# Startgate_Controller_Motherboard.net
KiCad netlist of a schematic drawn in EAGLE
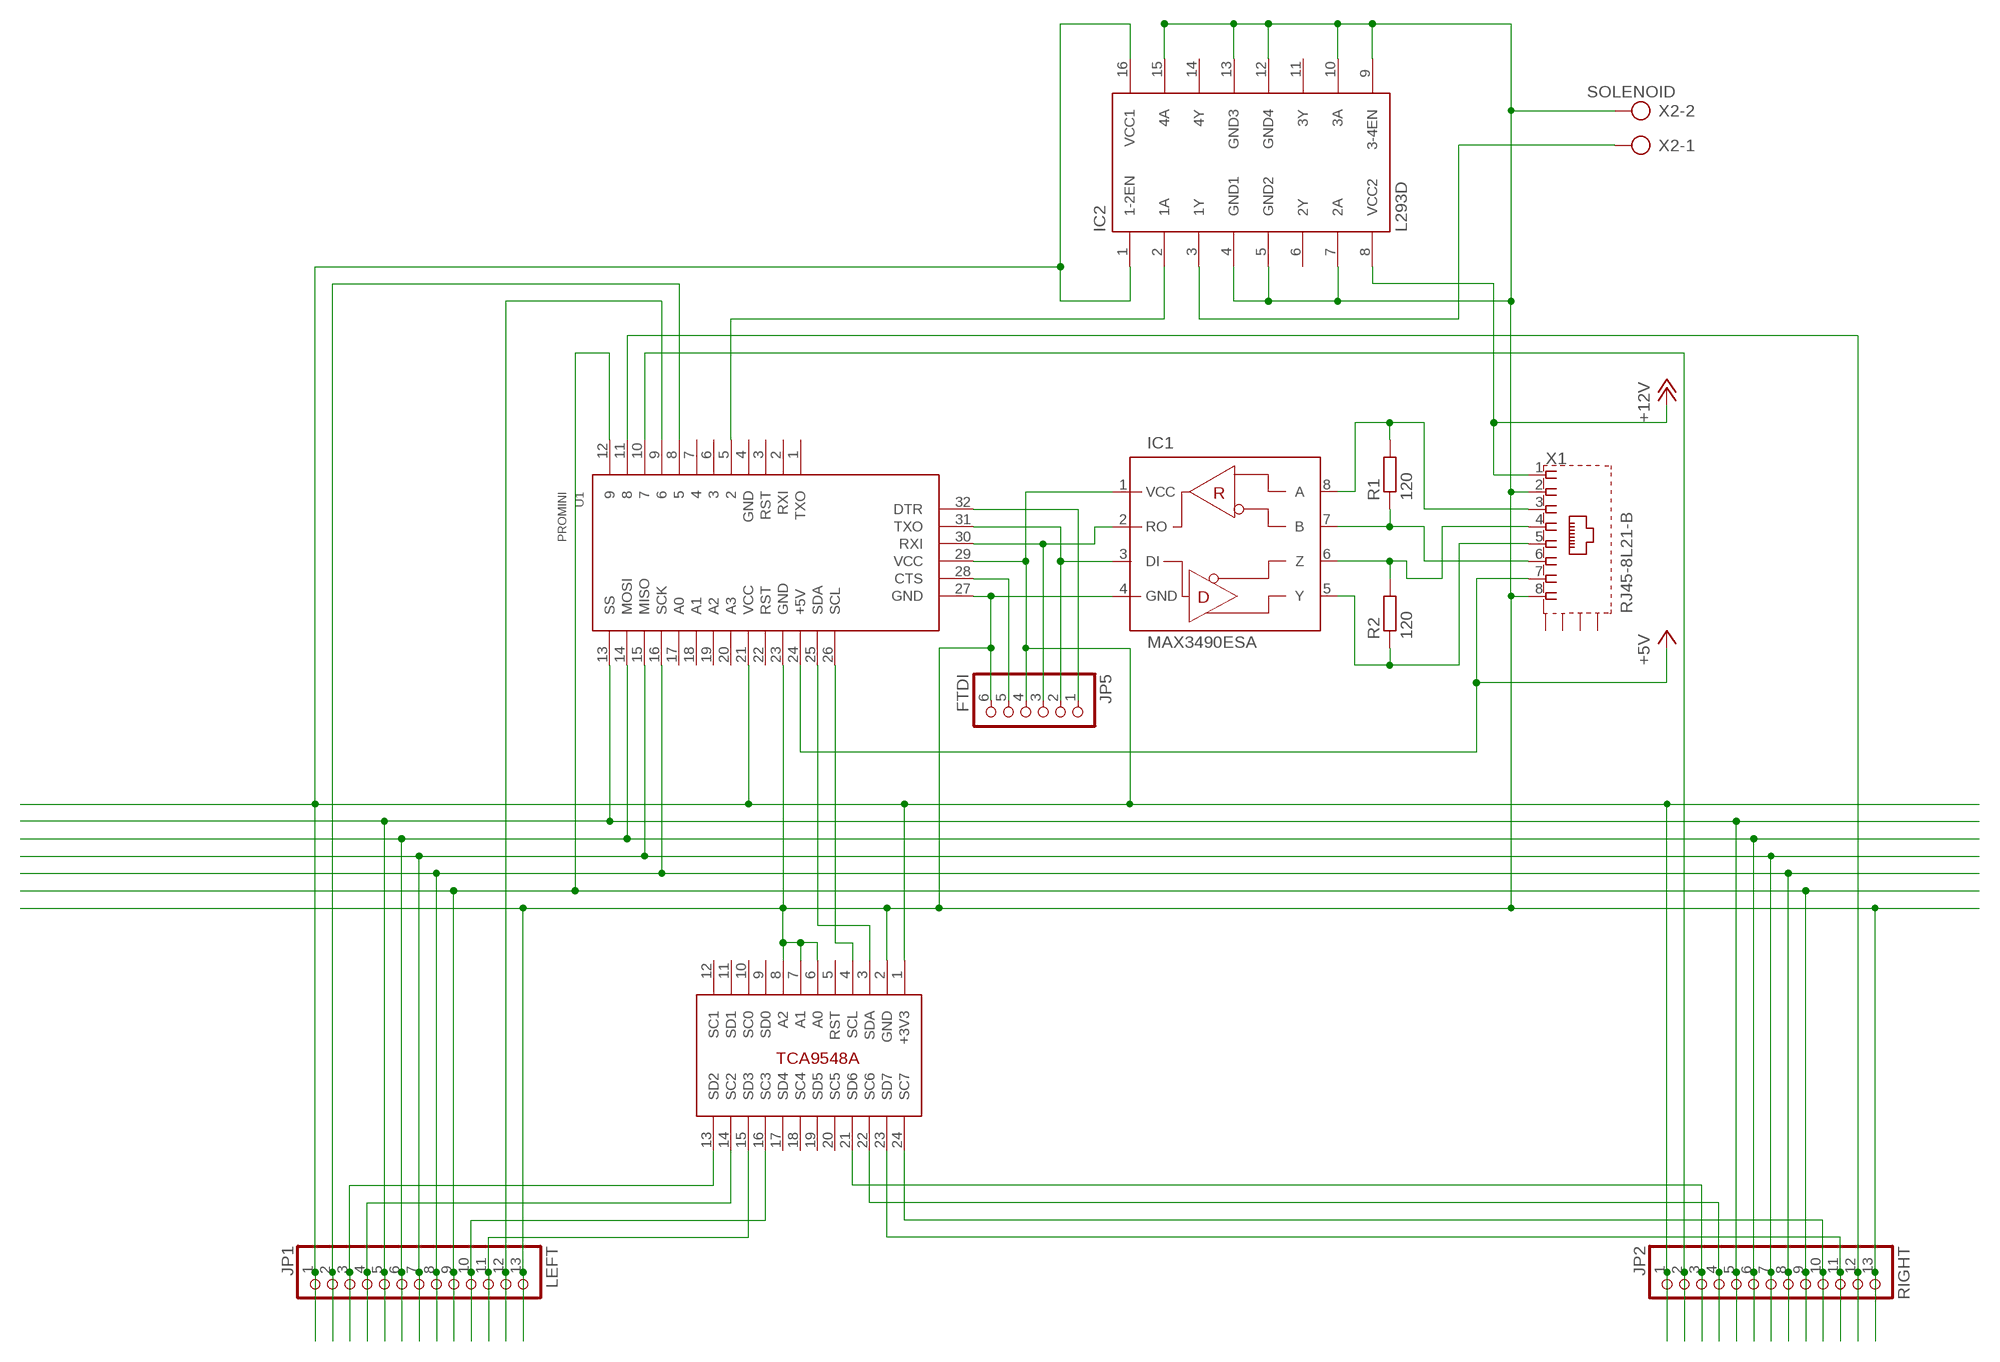
[diagram p0: schematic, sheet 1]

(export (version "E")
  (design (tool "Eeschema 10.0.6"))
  (components
    (comp (ref "IC1")
      (value "MAX3490ESA")
      (footprint "eagle-import:SO08")
      (libsource (lib "eagle-import") (part "MAX3490ESA"))
    )
    (comp (ref "IC2")
      (value "L293D")
      (footprint "eagle-import:DIL16")
      (libsource (lib "eagle-import") (part "L293D"))
    )
    (comp (ref "JP1")
      (value "LEFT")
      (footprint "eagle-import:1X13")
      (libsource (lib "eagle-import") (part "PINHD-1X13"))
    )
    (comp (ref "JP2")
      (value "RIGHT")
      (footprint "eagle-import:1X13")
      (libsource (lib "eagle-import") (part "PINHD-1X13"))
    )
    (comp (ref "JP5")
      (value "FTDI")
      (footprint "eagle-import:1X06")
      (libsource (lib "eagle-import") (part "PINHD-1X6"))
    )
    (comp (ref "R1")
      (value "120")
      (footprint "eagle-import:R0805")
      (libsource (lib "eagle-import") (part "R-EU_R0805"))
    )
    (comp (ref "R2")
      (value "120")
      (footprint "eagle-import:R0805")
      (libsource (lib "eagle-import") (part "R-EU_R0805"))
    )
    (comp (ref "U1")
      (value "PROMINI")
      (footprint "eagle-import:ARDUINOPROMINI")
      (libsource (lib "eagle-import") (part "ARDUINOPROMINI"))
    )
    (comp (ref "U2")
      (value "TCA9548A")
      (footprint "eagle-import:DIL24")
      (libsource (lib "eagle-import") (part "TCA9548A"))
    )
    (comp (ref "X1")
      (value "RJ45-8L21-B")
      (footprint "eagle-import:RJ45-SHIELD1")
      (libsource (lib "eagle-import") (part "RJ4521-B-8L"))
    )
    (comp (ref "X2")
      (value "SOLENOID")
      (footprint "eagle-import:AK300_2")
      (libsource (lib "eagle-import") (part "AK300/2"))
    )
  )
  (nets
    (net (code "1") (name "+5V") (class "Default")
      (node (ref "U1") (pin "24") (pinfunction "+5V_24") (pintype "power_in"))
      (node (ref "X1") (pin "7") (pinfunction "7_7") (pintype "passive"))
    )
    (net (code "2") (name "+12V") (class "Default")
      (node (ref "IC2") (pin "8") (pinfunction "VCC2_8") (pintype "power_in"))
      (node (ref "X1") (pin "1") (pinfunction "1_1") (pintype "passive"))
    )
    (net (code "3") (name "Net-(IC1-A)") (class "Default")
      (node (ref "IC1") (pin "8") (pinfunction "A_8") (pintype "input"))
      (node (ref "R1") (pin "2") (pinfunction "2_2") (pintype "passive"))
      (node (ref "X1") (pin "3") (pinfunction "3_3") (pintype "passive"))
    )
    (net (code "4") (name "Net-(IC1-B)") (class "Default")
      (node (ref "IC1") (pin "7") (pinfunction "B_7") (pintype "input"))
      (node (ref "R1") (pin "1") (pinfunction "1_1") (pintype "passive"))
      (node (ref "X1") (pin "6") (pinfunction "6_6") (pintype "passive"))
    )
    (net (code "5") (name "Net-(IC1-DI)") (class "Default")
      (node (ref "IC1") (pin "3") (pinfunction "DI_3") (pintype "input"))
      (node (ref "JP5") (pin "2") (pinfunction "2_2") (pintype "passive"))
      (node (ref "U1") (pin "31") (pinfunction "TXO_31") (pintype "bidirectional"))
    )
    (net (code "6") (name "Net-(IC1-GND)") (class "Default")
      (node (ref "IC1") (pin "4") (pinfunction "GND_4") (pintype "power_in"))
      (node (ref "IC2") (pin "10") (pinfunction "3A_10") (pintype "input"))
      (node (ref "IC2") (pin "12") (pinfunction "GND4_12") (pintype "power_in"))
      (node (ref "IC2") (pin "13") (pinfunction "GND3_13") (pintype "power_in"))
      (node (ref "IC2") (pin "15") (pinfunction "4A_15") (pintype "input"))
      (node (ref "IC2") (pin "4") (pinfunction "GND1_4") (pintype "power_in"))
      (node (ref "IC2") (pin "5") (pinfunction "GND2_5") (pintype "power_in"))
      (node (ref "IC2") (pin "7") (pinfunction "2A_7") (pintype "input"))
      (node (ref "IC2") (pin "9") (pinfunction "3-4EN_9") (pintype "input"))
      (node (ref "JP1") (pin "13") (pinfunction "13_13") (pintype "passive"))
      (node (ref "JP2") (pin "13") (pinfunction "13_13") (pintype "passive"))
      (node (ref "JP5") (pin "6") (pinfunction "6_6") (pintype "passive"))
      (node (ref "U1") (pin "23") (pinfunction "GND_23") (pintype "bidirectional"))
      (node (ref "U1") (pin "27") (pinfunction "GND_27") (pintype "bidirectional"))
      (node (ref "U2") (pin "2") (pinfunction "GND_2") (pintype "power_in"))
      (node (ref "U2") (pin "6") (pinfunction "A0_6") (pintype "bidirectional"))
      (node (ref "U2") (pin "7") (pinfunction "A1_7") (pintype "bidirectional"))
      (node (ref "U2") (pin "8") (pinfunction "A2_8") (pintype "bidirectional"))
      (node (ref "X1") (pin "2") (pinfunction "2_2") (pintype "passive"))
      (node (ref "X1") (pin "8") (pinfunction "8_8") (pintype "passive"))
      (node (ref "X2") (pin "2") (pinfunction "KL_2") (pintype "passive"))
    )
    (net (code "7") (name "Net-(IC1-RO)") (class "Default")
      (node (ref "IC1") (pin "2") (pinfunction "RO_2") (pintype "output"))
      (node (ref "JP5") (pin "3") (pinfunction "3_3") (pintype "passive"))
      (node (ref "U1") (pin "30") (pinfunction "RXI_30") (pintype "bidirectional"))
    )
    (net (code "8") (name "Net-(IC1-VCC)") (class "Default")
      (node (ref "IC1") (pin "1") (pinfunction "VCC_1") (pintype "power_in"))
      (node (ref "IC2") (pin "1") (pinfunction "1-2EN_1") (pintype "input"))
      (node (ref "IC2") (pin "16") (pinfunction "VCC1_16") (pintype "power_in"))
      (node (ref "JP1") (pin "1") (pinfunction "1_1") (pintype "passive"))
      (node (ref "JP2") (pin "1") (pinfunction "1_1") (pintype "passive"))
      (node (ref "JP5") (pin "4") (pinfunction "4_4") (pintype "passive"))
      (node (ref "U1") (pin "21") (pinfunction "VCC_21") (pintype "bidirectional"))
      (node (ref "U1") (pin "29") (pinfunction "VCC_29") (pintype "bidirectional"))
      (node (ref "U2") (pin "1") (pinfunction "+3V3_1") (pintype "power_in"))
    )
    (net (code "9") (name "Net-(IC1-Y)") (class "Default")
      (node (ref "IC1") (pin "5") (pinfunction "Y_5") (pintype "output"))
      (node (ref "R2") (pin "1") (pinfunction "1_1") (pintype "passive"))
      (node (ref "X1") (pin "5") (pinfunction "5_5") (pintype "passive"))
    )
    (net (code "10") (name "Net-(IC1-Z)") (class "Default")
      (node (ref "IC1") (pin "6") (pinfunction "Z_6") (pintype "output"))
      (node (ref "R2") (pin "2") (pinfunction "2_2") (pintype "passive"))
      (node (ref "X1") (pin "4") (pinfunction "4_4") (pintype "passive"))
    )
    (net (code "11") (name "Net-(IC2-1A)") (class "Default")
      (node (ref "IC2") (pin "2") (pinfunction "1A_2") (pintype "input"))
      (node (ref "U1") (pin "5") (pinfunction "2_5") (pintype "bidirectional"))
    )
    (net (code "12") (name "Net-(IC2-1Y)") (class "Default")
      (node (ref "IC2") (pin "3") (pinfunction "1Y_3") (pintype "output"))
      (node (ref "X2") (pin "1") (pinfunction "KL_1") (pintype "passive"))
    )
    (net (code "13") (name "Net-(U1-5)") (class "Default")
      (node (ref "JP1") (pin "2") (pinfunction "2_2") (pintype "passive"))
      (node (ref "U1") (pin "8") (pinfunction "5_8") (pintype "bidirectional"))
    )
    (net (code "14") (name "Net-(U1-6)") (class "Default")
      (node (ref "JP1") (pin "12") (pinfunction "12_12") (pintype "passive"))
      (node (ref "U1") (pin "9") (pinfunction "6_9") (pintype "bidirectional"))
    )
    (net (code "15") (name "Net-(U1-7)") (class "Default")
      (node (ref "JP2") (pin "2") (pinfunction "2_2") (pintype "passive"))
      (node (ref "U1") (pin "10") (pinfunction "7_10") (pintype "bidirectional"))
    )
    (net (code "16") (name "Net-(U1-8)") (class "Default")
      (node (ref "JP2") (pin "12") (pinfunction "12_12") (pintype "passive"))
      (node (ref "U1") (pin "11") (pinfunction "8_11") (pintype "bidirectional"))
    )
    (net (code "17") (name "Net-(U1-9)") (class "Default")
      (node (ref "JP1") (pin "9") (pinfunction "9_9") (pintype "passive"))
      (node (ref "JP2") (pin "9") (pinfunction "9_9") (pintype "passive"))
      (node (ref "U1") (pin "12") (pinfunction "9_12") (pintype "bidirectional"))
    )
    (net (code "18") (name "Net-(U1-CTS)") (class "Default")
      (node (ref "JP5") (pin "5") (pinfunction "5_5") (pintype "passive"))
      (node (ref "U1") (pin "28") (pinfunction "CTS_28") (pintype "bidirectional"))
    )
    (net (code "19") (name "Net-(U1-DTR)") (class "Default")
      (node (ref "JP5") (pin "1") (pinfunction "1_1") (pintype "passive"))
      (node (ref "U1") (pin "32") (pinfunction "DTR_32") (pintype "bidirectional"))
    )
    (net (code "20") (name "Net-(U1-MISO)") (class "Default")
      (node (ref "JP1") (pin "7") (pinfunction "7_7") (pintype "passive"))
      (node (ref "JP2") (pin "7") (pinfunction "7_7") (pintype "passive"))
      (node (ref "U1") (pin "15") (pinfunction "MISO_15") (pintype "bidirectional"))
    )
    (net (code "21") (name "Net-(U1-MOSI)") (class "Default")
      (node (ref "JP1") (pin "6") (pinfunction "6_6") (pintype "passive"))
      (node (ref "JP2") (pin "6") (pinfunction "6_6") (pintype "passive"))
      (node (ref "U1") (pin "14") (pinfunction "MOSI_14") (pintype "bidirectional"))
    )
    (net (code "22") (name "Net-(U1-SCK)") (class "Default")
      (node (ref "JP1") (pin "8") (pinfunction "8_8") (pintype "passive"))
      (node (ref "JP2") (pin "8") (pinfunction "8_8") (pintype "passive"))
      (node (ref "U1") (pin "16") (pinfunction "SCK_16") (pintype "bidirectional"))
    )
    (net (code "23") (name "Net-(U1-SCL)") (class "Default")
      (node (ref "U1") (pin "26") (pinfunction "SCL_26") (pintype "bidirectional"))
      (node (ref "U2") (pin "4") (pinfunction "SCL_4") (pintype "bidirectional"))
    )
    (net (code "24") (name "Net-(U1-SDA)") (class "Default")
      (node (ref "U1") (pin "25") (pinfunction "SDA_25") (pintype "bidirectional"))
      (node (ref "U2") (pin "3") (pinfunction "SDA_3") (pintype "bidirectional"))
    )
    (net (code "25") (name "Net-(U1-SS)") (class "Default")
      (node (ref "JP1") (pin "5") (pinfunction "5_5") (pintype "passive"))
      (node (ref "JP2") (pin "5") (pinfunction "5_5") (pintype "passive"))
      (node (ref "U1") (pin "13") (pinfunction "SS_13") (pintype "bidirectional"))
    )
    (net (code "26") (name "Net-(U2-SC2)") (class "Default")
      (node (ref "JP1") (pin "4") (pinfunction "4_4") (pintype "passive"))
      (node (ref "U2") (pin "14") (pinfunction "SC2_14") (pintype "bidirectional"))
    )
    (net (code "27") (name "Net-(U2-SC3)") (class "Default")
      (node (ref "JP1") (pin "10") (pinfunction "10_10") (pintype "passive"))
      (node (ref "U2") (pin "16") (pinfunction "SC3_16") (pintype "bidirectional"))
    )
    (net (code "28") (name "Net-(U2-SC6)") (class "Default")
      (node (ref "JP2") (pin "4") (pinfunction "4_4") (pintype "passive"))
      (node (ref "U2") (pin "22") (pinfunction "SC6_22") (pintype "bidirectional"))
    )
    (net (code "29") (name "Net-(U2-SC7)") (class "Default")
      (node (ref "JP2") (pin "10") (pinfunction "10_10") (pintype "passive"))
      (node (ref "U2") (pin "24") (pinfunction "SC7_24") (pintype "bidirectional"))
    )
    (net (code "30") (name "Net-(U2-SD2)") (class "Default")
      (node (ref "JP1") (pin "3") (pinfunction "3_3") (pintype "passive"))
      (node (ref "U2") (pin "13") (pinfunction "SD2_13") (pintype "bidirectional"))
    )
    (net (code "31") (name "Net-(U2-SD3)") (class "Default")
      (node (ref "JP1") (pin "11") (pinfunction "11_11") (pintype "passive"))
      (node (ref "U2") (pin "15") (pinfunction "SD3_15") (pintype "bidirectional"))
    )
    (net (code "32") (name "Net-(U2-SD6)") (class "Default")
      (node (ref "JP2") (pin "3") (pinfunction "3_3") (pintype "passive"))
      (node (ref "U2") (pin "21") (pinfunction "SD6_21") (pintype "bidirectional"))
    )
    (net (code "33") (name "Net-(U2-SD7)") (class "Default")
      (node (ref "JP2") (pin "11") (pinfunction "11_11") (pintype "passive"))
      (node (ref "U2") (pin "23") (pinfunction "SD7_23") (pintype "bidirectional"))
    )
    (net (code "34") (name "unconnected-(IC2-2Y-Pad6)") (class "Default")
      (node (ref "IC2") (pin "6") (pinfunction "2Y_6") (pintype "output"))
    )
    (net (code "35") (name "unconnected-(IC2-3Y-Pad11)") (class "Default")
      (node (ref "IC2") (pin "11") (pinfunction "3Y_11") (pintype "output"))
    )
    (net (code "36") (name "unconnected-(IC2-4Y-Pad14)") (class "Default")
      (node (ref "IC2") (pin "14") (pinfunction "4Y_14") (pintype "output"))
    )
    (net (code "37") (name "unconnected-(U1-3-Pad6)") (class "Default")
      (node (ref "U1") (pin "6") (pinfunction "3_6") (pintype "bidirectional"))
    )
    (net (code "38") (name "unconnected-(U1-4-Pad7)") (class "Default")
      (node (ref "U1") (pin "7") (pinfunction "4_7") (pintype "bidirectional"))
    )
    (net (code "39") (name "unconnected-(U1-A0-Pad17)") (class "Default")
      (node (ref "U1") (pin "17") (pinfunction "A0_17") (pintype "bidirectional"))
    )
    (net (code "40") (name "unconnected-(U1-A1-Pad18)") (class "Default")
      (node (ref "U1") (pin "18") (pinfunction "A1_18") (pintype "bidirectional"))
    )
    (net (code "41") (name "unconnected-(U1-A2-Pad19)") (class "Default")
      (node (ref "U1") (pin "19") (pinfunction "A2_19") (pintype "bidirectional"))
    )
    (net (code "42") (name "unconnected-(U1-A3-Pad20)") (class "Default")
      (node (ref "U1") (pin "20") (pinfunction "A3_20") (pintype "bidirectional"))
    )
    (net (code "43") (name "unconnected-(U1-GND-Pad4)") (class "Default")
      (node (ref "U1") (pin "4") (pinfunction "GND_4") (pintype "bidirectional"))
    )
    (net (code "44") (name "unconnected-(U1-RST-Pad3)") (class "Default")
      (node (ref "U1") (pin "3") (pinfunction "RST_3") (pintype "bidirectional"))
    )
    (net (code "45") (name "unconnected-(U1-RST-Pad22)") (class "Default")
      (node (ref "U1") (pin "22") (pinfunction "RST_22") (pintype "bidirectional"))
    )
    (net (code "46") (name "unconnected-(U1-RXI-Pad2)") (class "Default")
      (node (ref "U1") (pin "2") (pinfunction "RXI_2") (pintype "bidirectional"))
    )
    (net (code "47") (name "unconnected-(U1-TXO-Pad1)") (class "Default")
      (node (ref "U1") (pin "1") (pinfunction "TXO_1") (pintype "bidirectional"))
    )
    (net (code "48") (name "unconnected-(U2-RST-Pad5)") (class "Default")
      (node (ref "U2") (pin "5") (pinfunction "RST_5") (pintype "bidirectional"))
    )
    (net (code "49") (name "unconnected-(U2-SC0-Pad10)") (class "Default")
      (node (ref "U2") (pin "10") (pinfunction "SC0_10") (pintype "bidirectional"))
    )
    (net (code "50") (name "unconnected-(U2-SC1-Pad12)") (class "Default")
      (node (ref "U2") (pin "12") (pinfunction "SC1_12") (pintype "bidirectional"))
    )
    (net (code "51") (name "unconnected-(U2-SC4-Pad18)") (class "Default")
      (node (ref "U2") (pin "18") (pinfunction "SC4_18") (pintype "bidirectional"))
    )
    (net (code "52") (name "unconnected-(U2-SC5-Pad20)") (class "Default")
      (node (ref "U2") (pin "20") (pinfunction "SC5_20") (pintype "bidirectional"))
    )
    (net (code "53") (name "unconnected-(U2-SD0-Pad9)") (class "Default")
      (node (ref "U2") (pin "9") (pinfunction "SD0_9") (pintype "bidirectional"))
    )
    (net (code "54") (name "unconnected-(U2-SD1-Pad11)") (class "Default")
      (node (ref "U2") (pin "11") (pinfunction "SD1_11") (pintype "bidirectional"))
    )
    (net (code "55") (name "unconnected-(U2-SD4-Pad17)") (class "Default")
      (node (ref "U2") (pin "17") (pinfunction "SD4_17") (pintype "bidirectional"))
    )
    (net (code "56") (name "unconnected-(U2-SD5-Pad19)") (class "Default")
      (node (ref "U2") (pin "19") (pinfunction "SD5_19") (pintype "bidirectional"))
    )
    (net (code "57") (name "unconnected-(X1-S-PadS1)") (class "Default")
      (node (ref "X1") (pin "S1") (pinfunction "S_S1") (pintype "passive"))
    )
    (net (code "58") (name "unconnected-(X1-S-PadS2)") (class "Default")
      (node (ref "X1") (pin "S2") (pinfunction "S_S2") (pintype "passive"))
    )
    (net (code "59") (name "unconnected-(X1-S-PadS3)") (class "Default")
      (node (ref "X1") (pin "S3") (pinfunction "S_S3") (pintype "passive"))
    )
    (net (code "60") (name "unconnected-(X1-S-PadS4)") (class "Default")
      (node (ref "X1") (pin "S4") (pinfunction "S_S4") (pintype "passive"))
    )
  )
)
